# pet_dispenser.net
KiCad netlist of a schematic drawn in EasyEDA Pro
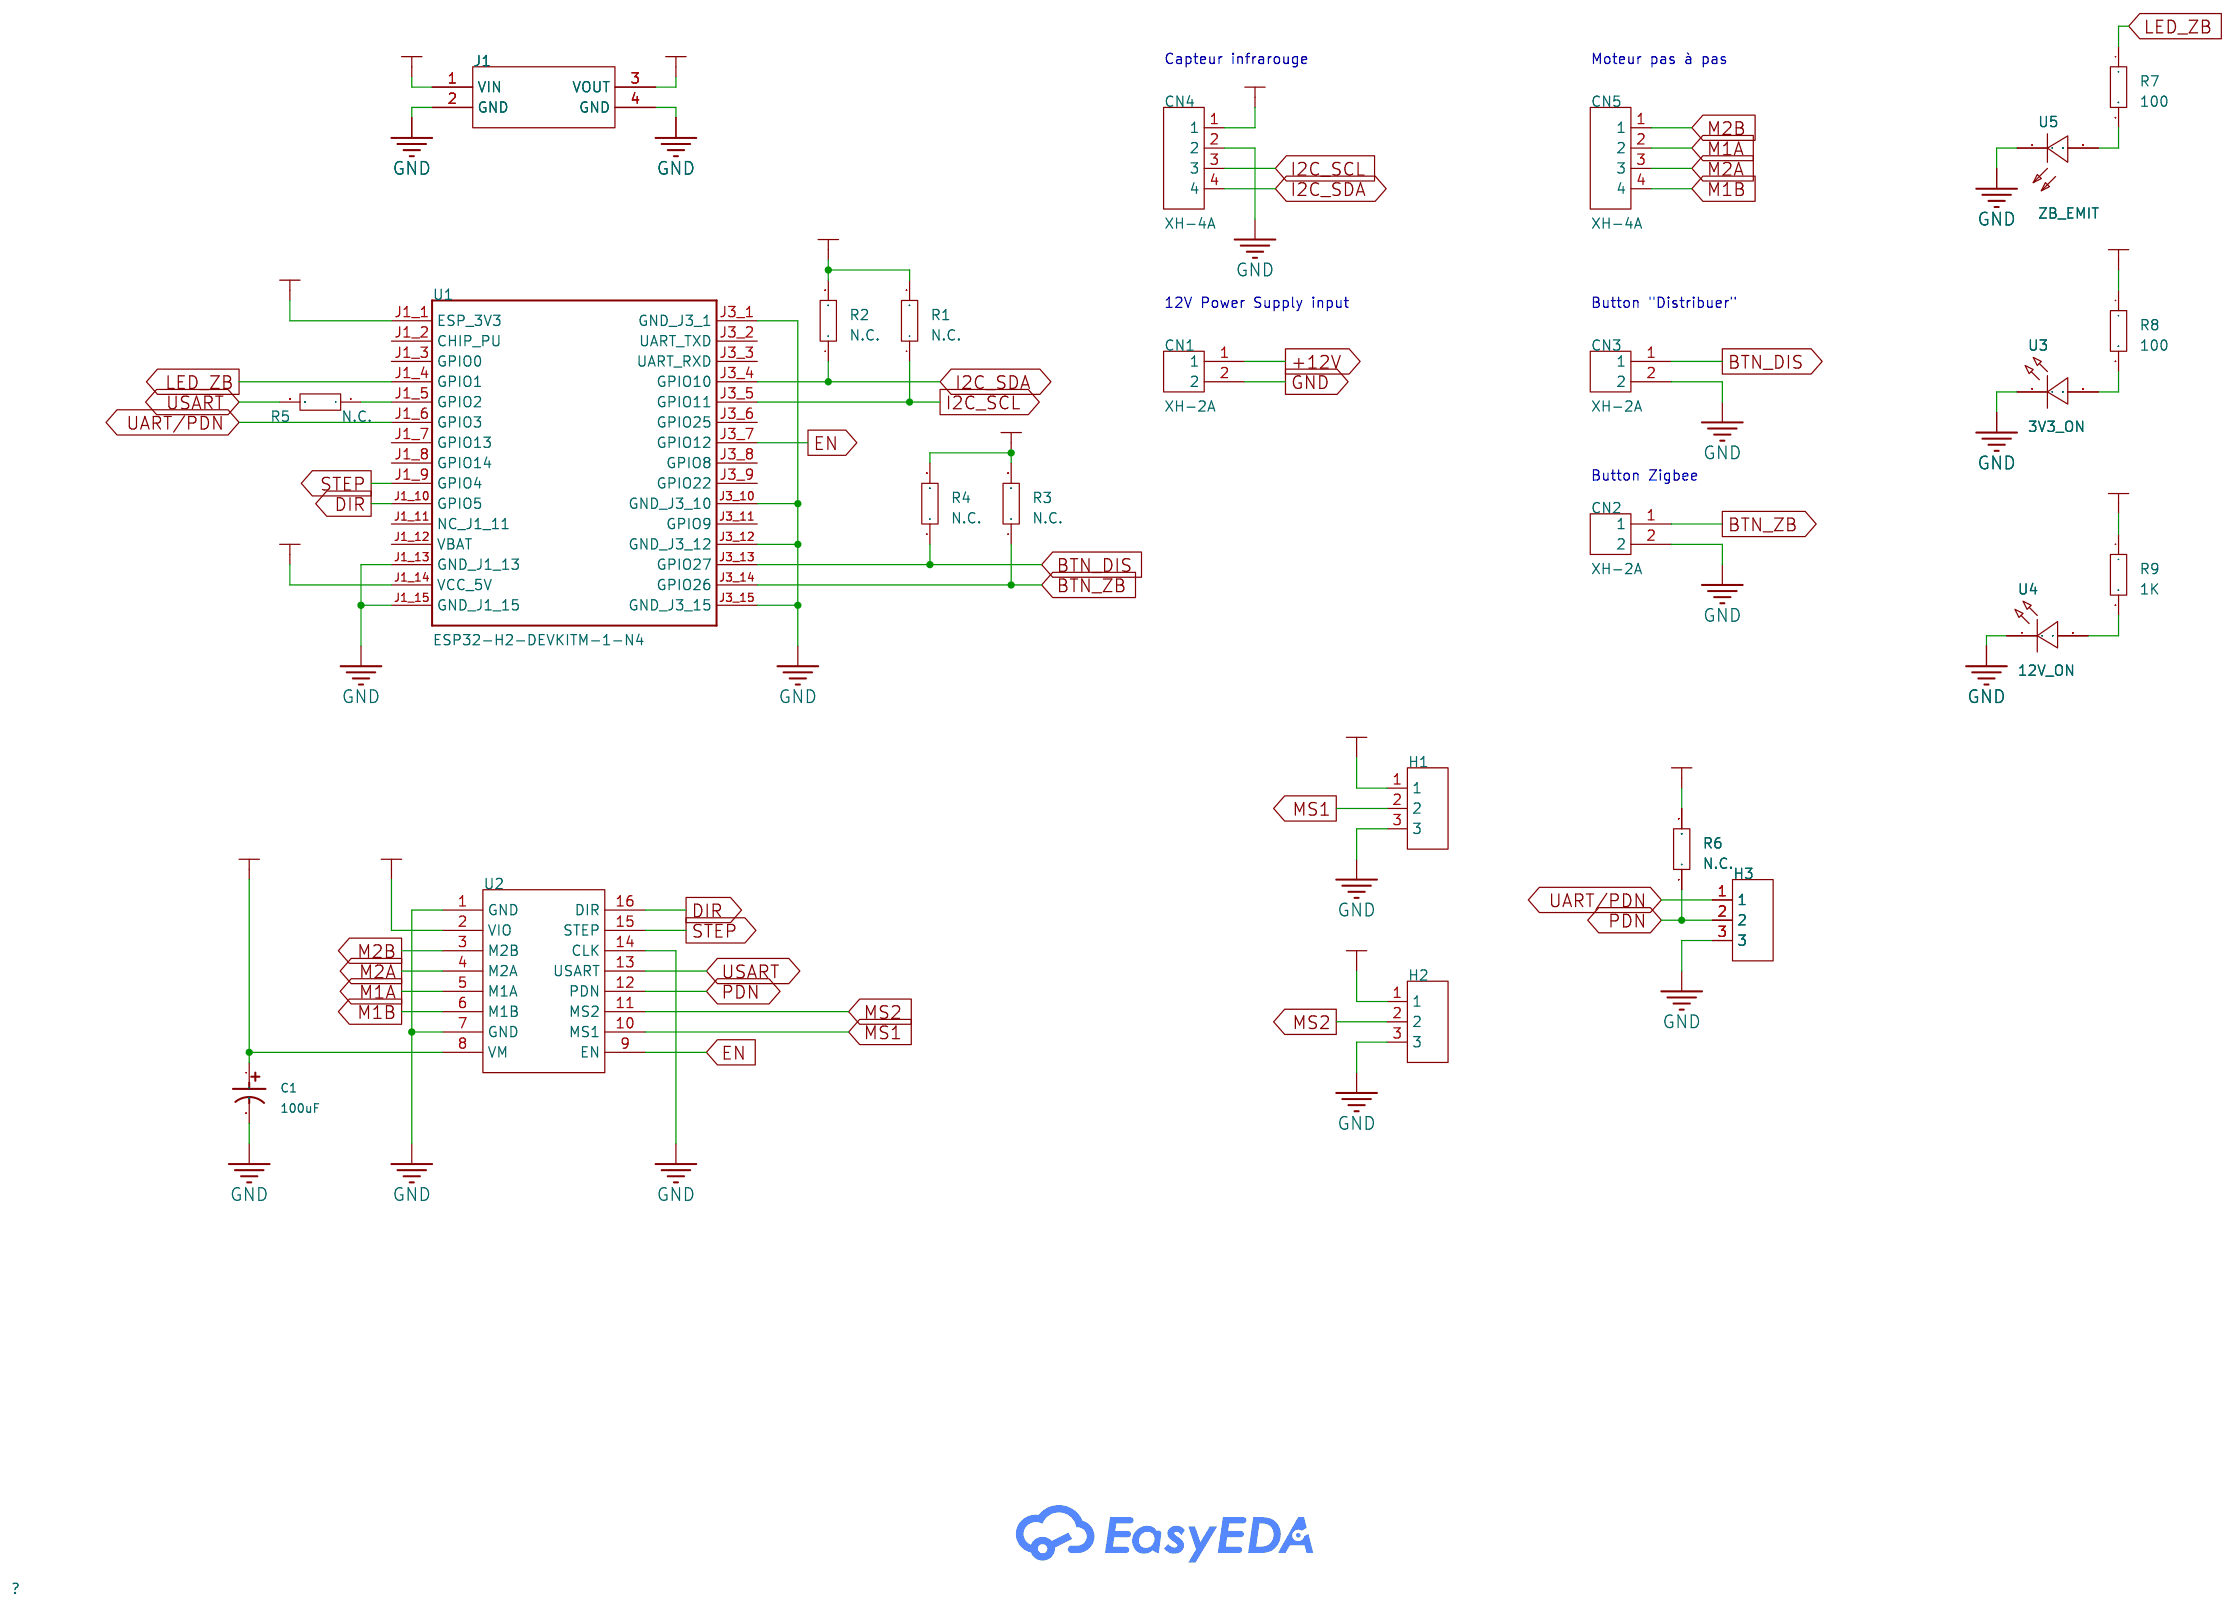
[diagram p0: schematic sheet]

(export (version "E")
  (design (tool "Eeschema 10.0.6"))
  (components
    (comp (ref "C1")
      (value "100uF")
      (footprint "easyedapro:CAP-TH_BD8.0-P3.50-D0.6-FD-H12.0")
      (fields (field (name "Manufacturer Part") "ERS1HM101F12OT") (field (name "Manufacturer") "AISHI(艾华集团)"))
      (libsource (lib "easyedapro") (part "ERS1HM101F12OT"))
    )
    (comp (ref "CN1")
      (value "XH-2A")
      (footprint "easyedapro:CONN-TH_XH-2A")
      (fields (field (name "Manufacturer") "BOOMELE(博穆精密)"))
      (libsource (lib "easyedapro") (part "XH-2A"))
    )
    (comp (ref "CN2")
      (value "XH-2A")
      (footprint "easyedapro:CONN-TH_XH-2A")
      (fields (field (name "Manufacturer") "BOOMELE(博穆精密)"))
      (libsource (lib "easyedapro") (part "XH-2A"))
    )
    (comp (ref "CN3")
      (value "XH-2A")
      (footprint "easyedapro:CONN-TH_XH-2A")
      (fields (field (name "Manufacturer") "BOOMELE(博穆精密)"))
      (libsource (lib "easyedapro") (part "XH-2A"))
    )
    (comp (ref "CN4")
      (value "XH-4A")
      (footprint "easyedapro:CONN-TH_4P-P2.50_4PIN")
      (fields (field (name "Manufacturer") "LXWCONN(连兴旺电子)"))
      (libsource (lib "easyedapro") (part "XH-4A_C53055480"))
    )
    (comp (ref "CN5")
      (value "XH-4A")
      (footprint "easyedapro:CONN-TH_4P-P2.50_4PIN")
      (fields (field (name "Manufacturer") "LXWCONN(连兴旺电子)"))
      (libsource (lib "easyedapro") (part "XH-4A_C53055480"))
    )
    (comp (ref "H1")
      (value "HX PH254-01-03-Z-L11.5 pcb pin header")
      (footprint "easyedapro:HDR-TH_3P-P2.54-V-M-1")
      (fields (field (name "Manufacturer") "hanxia(韩下)"))
      (libsource (lib "easyedapro") (part "HX PH254-01-03-Z-L11.5 PCB PIN HEADER"))
    )
    (comp (ref "H2")
      (value "HX PH254-01-03-Z-L11.5 pcb pin header")
      (footprint "easyedapro:HDR-TH_3P-P2.54-V-M-1")
      (fields (field (name "Manufacturer") "hanxia(韩下)"))
      (libsource (lib "easyedapro") (part "HX PH254-01-03-Z-L11.5 PCB PIN HEADER"))
    )
    (comp (ref "H3")
      (value "HX PH254-01-03-Z-L11.5 pcb pin header")
      (footprint "easyedapro:HDR-TH_3P-P2.54-V-M-1")
      (fields (field (name "Manufacturer") "hanxia(韩下)"))
      (libsource (lib "easyedapro") (part "HX PH254-01-03-Z-L11.5 PCB PIN HEADER"))
    )
    (comp (ref "J1")
      (value "~")
      (footprint "easyedapro:LM2596S")
      (libsource (lib "easyedapro") (part "LM2596S"))
    )
    (comp (ref "R1")
      (value "N.C.")
      (footprint "easyedapro:R0603")
      (fields (field (name "Manufacturer Part") "MFR-25FTE52-4K7") (field (name "Manufacturer") "YAGEO(国巨)"))
      (libsource (lib "easyedapro") (part "Res"))
    )
    (comp (ref "R2")
      (value "N.C.")
      (footprint "easyedapro:R0603")
      (fields (field (name "Manufacturer Part") "MFR-25FTE52-4K7") (field (name "Manufacturer") "YAGEO(国巨)"))
      (libsource (lib "easyedapro") (part "Res"))
    )
    (comp (ref "R3")
      (value "N.C.")
      (footprint "easyedapro:R0603")
      (fields (field (name "Manufacturer Part") "MFR-25FTE52-4K7") (field (name "Manufacturer") "YAGEO(国巨)"))
      (libsource (lib "easyedapro") (part "Res"))
    )
    (comp (ref "R4")
      (value "N.C.")
      (footprint "easyedapro:R0603")
      (fields (field (name "Manufacturer Part") "MFR-25FTE52-4K7") (field (name "Manufacturer") "YAGEO(国巨)"))
      (libsource (lib "easyedapro") (part "Res"))
    )
    (comp (ref "R5")
      (value "N.C.")
      (footprint "easyedapro:R0603")
      (fields (field (name "Manufacturer Part") "MFR-25FTE52-4K7") (field (name "Manufacturer") "YAGEO(国巨)"))
      (libsource (lib "easyedapro") (part "Res"))
    )
    (comp (ref "R6")
      (value "N.C.")
      (footprint "easyedapro:R0603")
      (fields (field (name "Manufacturer Part") "MFR-25FTE52-4K7") (field (name "Manufacturer") "YAGEO(国巨)"))
      (libsource (lib "easyedapro") (part "Res"))
    )
    (comp (ref "R7")
      (value "100")
      (footprint "easyedapro:R0603")
      (fields (field (name "Manufacturer Part") "MFR-25FTE52-4K7") (field (name "Manufacturer") "YAGEO(国巨)"))
      (libsource (lib "easyedapro") (part "Res"))
    )
    (comp (ref "R8")
      (value "100")
      (footprint "easyedapro:R0603")
      (fields (field (name "Manufacturer Part") "MFR-25FTE52-4K7") (field (name "Manufacturer") "YAGEO(国巨)"))
      (libsource (lib "easyedapro") (part "Res"))
    )
    (comp (ref "R9")
      (value "1K")
      (footprint "easyedapro:R0603")
      (fields (field (name "Manufacturer Part") "MFR-25FTE52-4K7") (field (name "Manufacturer") "YAGEO(国巨)"))
      (libsource (lib "easyedapro") (part "Res"))
    )
    (comp (ref "U1")
      (value "ESP32-H2-DEVKITM-1-N4")
      (footprint "easyedapro:MODULE_ESP32-H2-DEVKITM-1-N4")
      (libsource (lib "easyedapro") (part "ESP32-H2-DEVKITM-1-N4"))
    )
    (comp (ref "U2")
      (value "~")
      (footprint "easyedapro:TMC2209-radiator")
      (libsource (lib "easyedapro") (part "TMC2209-radiator"))
    )
    (comp (ref "U3")
      (value "3V3_ON")
      (footprint "easyedapro:LED-TH_BD3.9-P2.54-RD")
      (fields (field (name "Manufacturer Part") "greenled_m3"))
      (libsource (lib "easyedapro") (part "GREENLED_M3"))
    )
    (comp (ref "U4")
      (value "12V_ON")
      (footprint "easyedapro:LED-TH_BD3.9-P2.54-RD")
      (fields (field (name "Manufacturer Part") "greenled_m3"))
      (libsource (lib "easyedapro") (part "GREENLED_M3"))
    )
    (comp (ref "U5")
      (value "ZB_EMIT")
      (footprint "easyedapro:LED-TH_BD4.0-P2.00-D0.5-RD_BULE")
      (fields (field (name "Manufacturer Part") "LED-DIP-3MM_Blue"))
      (libsource (lib "easyedapro") (part "LED-DIP-3MM_BLUE"))
    )
  )
  (nets
    (net (code "1") (name "+3V3") (class "Default")
      (node (ref "CN4") (pin "1") (pinfunction "1_1") (pintype "unspecified"))
      (node (ref "H1") (pin "1") (pinfunction "1_1") (pintype "unspecified"))
      (node (ref "H2") (pin "1") (pinfunction "1_1") (pintype "unspecified"))
      (node (ref "R1") (pin "2") (pinfunction "2_2") (pintype "input"))
      (node (ref "R2") (pin "2") (pinfunction "2_2") (pintype "input"))
      (node (ref "R3") (pin "2") (pinfunction "2_2") (pintype "input"))
      (node (ref "R4") (pin "2") (pinfunction "2_2") (pintype "input"))
      (node (ref "R6") (pin "2") (pinfunction "2_2") (pintype "input"))
      (node (ref "R8") (pin "1") (pinfunction "1_1") (pintype "input"))
      (node (ref "U1") (pin "J1_1") (pinfunction "ESP_3V3_J1_1") (pintype "unspecified"))
      (node (ref "U2") (pin "2") (pinfunction "VIO_2") (pintype "input"))
    )
    (net (code "2") (name "+5V") (class "Default")
      (node (ref "J1") (pin "3") (pinfunction "VOUT_3") (pintype "input"))
      (node (ref "U1") (pin "J1_14") (pinfunction "VCC_5V_J1_14") (pintype "unspecified"))
    )
    (net (code "3") (name "+12V") (class "Default")
      (node (ref "C1") (pin "1") (pinfunction "1_1") (pintype "input"))
      (node (ref "CN1") (pin "1") (pinfunction "1_1") (pintype "unspecified"))
      (node (ref "J1") (pin "1") (pinfunction "VIN_1") (pintype "input"))
      (node (ref "R9") (pin "1") (pinfunction "1_1") (pintype "input"))
      (node (ref "U2") (pin "8") (pinfunction "VM_8") (pintype "input"))
    )
    (net (code "4") (name "BTN_DIS") (class "Default")
      (node (ref "CN3") (pin "1") (pinfunction "1_1") (pintype "unspecified"))
      (node (ref "R4") (pin "1") (pinfunction "1_1") (pintype "input"))
      (node (ref "U1") (pin "J3_13") (pinfunction "GPIO27_J3_13") (pintype "bidirectional"))
    )
    (net (code "5") (name "BTN_ZB") (class "Default")
      (node (ref "CN2") (pin "1") (pinfunction "1_1") (pintype "unspecified"))
      (node (ref "R3") (pin "1") (pinfunction "1_1") (pintype "input"))
      (node (ref "U1") (pin "J3_14") (pinfunction "GPIO26_J3_14") (pintype "bidirectional"))
    )
    (net (code "6") (name "DIR") (class "Default")
      (node (ref "U1") (pin "J1_10") (pinfunction "GPIO5_J1_10") (pintype "bidirectional"))
      (node (ref "U2") (pin "16") (pinfunction "DIR_16") (pintype "input"))
    )
    (net (code "7") (name "EN") (class "Default")
      (node (ref "U1") (pin "J3_7") (pinfunction "GPIO12_J3_7") (pintype "bidirectional"))
      (node (ref "U2") (pin "9") (pinfunction "EN_9") (pintype "input"))
    )
    (net (code "8") (name "GND") (class "Default")
      (node (ref "C1") (pin "2") (pinfunction "2_2") (pintype "input"))
      (node (ref "CN1") (pin "2") (pinfunction "2_2") (pintype "unspecified"))
      (node (ref "CN2") (pin "2") (pinfunction "2_2") (pintype "unspecified"))
      (node (ref "CN3") (pin "2") (pinfunction "2_2") (pintype "unspecified"))
      (node (ref "CN4") (pin "2") (pinfunction "2_2") (pintype "unspecified"))
      (node (ref "H1") (pin "3") (pinfunction "3_3") (pintype "unspecified"))
      (node (ref "H2") (pin "3") (pinfunction "3_3") (pintype "unspecified"))
      (node (ref "H3") (pin "3") (pinfunction "3_3") (pintype "unspecified"))
      (node (ref "J1") (pin "2") (pinfunction "GND_2") (pintype "input"))
      (node (ref "J1") (pin "4") (pinfunction "GND_4") (pintype "input"))
      (node (ref "U1") (pin "J1_13") (pinfunction "GND_J1_13_J1_13") (pintype "unspecified"))
      (node (ref "U1") (pin "J1_15") (pinfunction "GND_J1_15_J1_15") (pintype "unspecified"))
      (node (ref "U1") (pin "J3_1") (pinfunction "GND_J3_1_J3_1") (pintype "unspecified"))
      (node (ref "U1") (pin "J3_10") (pinfunction "GND_J3_10_J3_10") (pintype "unspecified"))
      (node (ref "U1") (pin "J3_12") (pinfunction "GND_J3_12_J3_12") (pintype "unspecified"))
      (node (ref "U1") (pin "J3_15") (pinfunction "GND_J3_15_J3_15") (pintype "unspecified"))
      (node (ref "U2") (pin "1") (pinfunction "GND_1") (pintype "input"))
      (node (ref "U2") (pin "14") (pinfunction "CLK_14") (pintype "input"))
      (node (ref "U2") (pin "7") (pinfunction "GND_7") (pintype "input"))
      (node (ref "U3") (pin "1") (pinfunction "1_1") (pintype "unspecified"))
      (node (ref "U4") (pin "1") (pinfunction "1_1") (pintype "unspecified"))
      (node (ref "U5") (pin "1") (pinfunction "1_1") (pintype "unspecified"))
    )
    (net (code "9") (name "I2C_SCL") (class "Default")
      (node (ref "CN4") (pin "3") (pinfunction "3_3") (pintype "unspecified"))
      (node (ref "R1") (pin "1") (pinfunction "1_1") (pintype "input"))
      (node (ref "U1") (pin "J3_5") (pinfunction "GPIO11_J3_5") (pintype "bidirectional"))
    )
    (net (code "10") (name "I2C_SDA") (class "Default")
      (node (ref "CN4") (pin "4") (pinfunction "4_4") (pintype "unspecified"))
      (node (ref "R2") (pin "1") (pinfunction "1_1") (pintype "input"))
      (node (ref "U1") (pin "J3_4") (pinfunction "GPIO10_J3_4") (pintype "bidirectional"))
    )
    (net (code "11") (name "LED_ZB") (class "Default")
      (node (ref "R7") (pin "1") (pinfunction "1_1") (pintype "input"))
      (node (ref "U1") (pin "J1_4") (pinfunction "GPIO1_J1_4") (pintype "bidirectional"))
    )
    (net (code "12") (name "M1A") (class "Default")
      (node (ref "CN5") (pin "2") (pinfunction "2_2") (pintype "unspecified"))
      (node (ref "U2") (pin "5") (pinfunction "M1A_5") (pintype "input"))
    )
    (net (code "13") (name "M1B") (class "Default")
      (node (ref "CN5") (pin "4") (pinfunction "4_4") (pintype "unspecified"))
      (node (ref "U2") (pin "6") (pinfunction "M1B_6") (pintype "input"))
    )
    (net (code "14") (name "M2A") (class "Default")
      (node (ref "CN5") (pin "3") (pinfunction "3_3") (pintype "unspecified"))
      (node (ref "U2") (pin "4") (pinfunction "M2A_4") (pintype "input"))
    )
    (net (code "15") (name "M2B") (class "Default")
      (node (ref "CN5") (pin "1") (pinfunction "1_1") (pintype "unspecified"))
      (node (ref "U2") (pin "3") (pinfunction "M2B_3") (pintype "input"))
    )
    (net (code "16") (name "MS1") (class "Default")
      (node (ref "H1") (pin "2") (pinfunction "2_2") (pintype "unspecified"))
      (node (ref "U2") (pin "10") (pinfunction "MS1_10") (pintype "input"))
    )
    (net (code "17") (name "MS2") (class "Default")
      (node (ref "H2") (pin "2") (pinfunction "2_2") (pintype "unspecified"))
      (node (ref "U2") (pin "11") (pinfunction "MS2_11") (pintype "input"))
    )
    (net (code "18") (name "Net-(R7-Pad2)") (class "Default")
      (node (ref "R7") (pin "2") (pinfunction "2_2") (pintype "input"))
      (node (ref "U5") (pin "2") (pinfunction "2_2") (pintype "unspecified"))
    )
    (net (code "19") (name "Net-(R8-Pad2)") (class "Default")
      (node (ref "R8") (pin "2") (pinfunction "2_2") (pintype "input"))
      (node (ref "U3") (pin "2") (pinfunction "2_2") (pintype "unspecified"))
    )
    (net (code "20") (name "Net-(R9-Pad2)") (class "Default")
      (node (ref "R9") (pin "2") (pinfunction "2_2") (pintype "input"))
      (node (ref "U4") (pin "2") (pinfunction "2_2") (pintype "unspecified"))
    )
    (net (code "21") (name "Net-(U1-GPIO2)") (class "Default")
      (node (ref "R5") (pin "1") (pinfunction "1_1") (pintype "input"))
      (node (ref "U1") (pin "J1_5") (pinfunction "GPIO2_J1_5") (pintype "bidirectional"))
    )
    (net (code "22") (name "PDN") (class "Default")
      (node (ref "H3") (pin "2") (pinfunction "2_2") (pintype "unspecified"))
      (node (ref "R6") (pin "1") (pinfunction "1_1") (pintype "input"))
      (node (ref "U2") (pin "12") (pinfunction "PDN_12") (pintype "input"))
    )
    (net (code "23") (name "STEP") (class "Default")
      (node (ref "U1") (pin "J1_9") (pinfunction "GPIO4_J1_9") (pintype "bidirectional"))
      (node (ref "U2") (pin "15") (pinfunction "STEP_15") (pintype "input"))
    )
    (net (code "24") (name "UART{slash}PDN") (class "Default")
      (node (ref "H3") (pin "1") (pinfunction "1_1") (pintype "unspecified"))
      (node (ref "U1") (pin "J1_6") (pinfunction "GPIO3_J1_6") (pintype "bidirectional"))
    )
    (net (code "25") (name "USART") (class "Default")
      (node (ref "R5") (pin "2") (pinfunction "2_2") (pintype "input"))
      (node (ref "U2") (pin "13") (pinfunction "USART_13") (pintype "input"))
    )
    (net (code "26") (name "unconnected-(U1-CHIP_PU-PadJ1_2)") (class "Default")
      (node (ref "U1") (pin "J1_2") (pinfunction "CHIP_PU_J1_2") (pintype "input"))
    )
    (net (code "27") (name "unconnected-(U1-GPIO0-PadJ1_3)") (class "Default")
      (node (ref "U1") (pin "J1_3") (pinfunction "GPIO0_J1_3") (pintype "bidirectional"))
    )
    (net (code "28") (name "unconnected-(U1-GPIO8-PadJ3_8)") (class "Default")
      (node (ref "U1") (pin "J3_8") (pinfunction "GPIO8_J3_8") (pintype "bidirectional"))
    )
    (net (code "29") (name "unconnected-(U1-GPIO9-PadJ3_11)") (class "Default")
      (node (ref "U1") (pin "J3_11") (pinfunction "GPIO9_J3_11") (pintype "bidirectional"))
    )
    (net (code "30") (name "unconnected-(U1-GPIO13-PadJ1_7)") (class "Default")
      (node (ref "U1") (pin "J1_7") (pinfunction "GPIO13_J1_7") (pintype "bidirectional"))
    )
    (net (code "31") (name "unconnected-(U1-GPIO14-PadJ1_8)") (class "Default")
      (node (ref "U1") (pin "J1_8") (pinfunction "GPIO14_J1_8") (pintype "bidirectional"))
    )
    (net (code "32") (name "unconnected-(U1-GPIO22-PadJ3_9)") (class "Default")
      (node (ref "U1") (pin "J3_9") (pinfunction "GPIO22_J3_9") (pintype "bidirectional"))
    )
    (net (code "33") (name "unconnected-(U1-GPIO25-PadJ3_6)") (class "Default")
      (node (ref "U1") (pin "J3_6") (pinfunction "GPIO25_J3_6") (pintype "bidirectional"))
    )
    (net (code "34") (name "unconnected-(U1-NC_J1_11-PadJ1_11)") (class "Default")
      (node (ref "U1") (pin "J1_11") (pinfunction "NC_J1_11_J1_11") (pintype "unspecified"))
    )
    (net (code "35") (name "unconnected-(U1-UART_RXD-PadJ3_3)") (class "Default")
      (node (ref "U1") (pin "J3_3") (pinfunction "UART_RXD_J3_3") (pintype "bidirectional"))
    )
    (net (code "36") (name "unconnected-(U1-UART_TXD-PadJ3_2)") (class "Default")
      (node (ref "U1") (pin "J3_2") (pinfunction "UART_TXD_J3_2") (pintype "bidirectional"))
    )
    (net (code "37") (name "unconnected-(U1-VBAT-PadJ1_12)") (class "Default")
      (node (ref "U1") (pin "J1_12") (pinfunction "VBAT_J1_12") (pintype "unspecified"))
    )
  )
)
